# gems-NHD.net
KiCad netlist of a schematic drawn in EAGLE
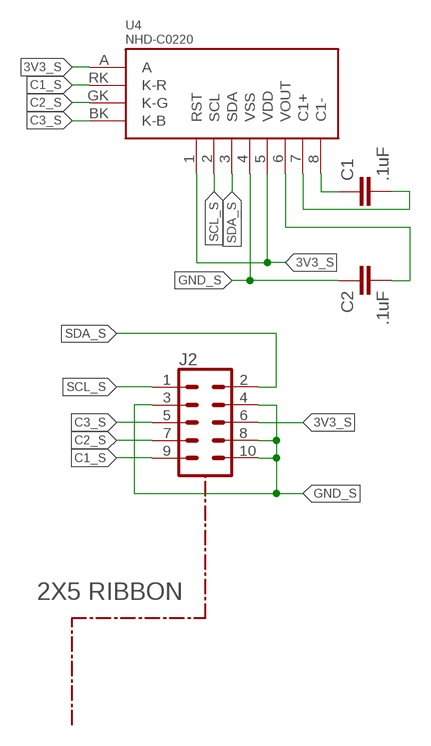
[diagram p0: schematic, sheet 1]

(export (version "E")
  (design (tool "Eeschema 10.0.6"))
  (components
    (comp (ref "C1")
      (value ".1uF")
      (footprint "eagle-import:C025-025X050")
      (libsource (lib "eagle-import") (part "C-EU025-025X050"))
    )
    (comp (ref "C2")
      (value ".1uF")
      (footprint "eagle-import:C025-025X050")
      (libsource (lib "eagle-import") (part "C-EU025-025X050"))
    )
    (comp (ref "J2")
      (value "CONN_05X2SHD-NS")
      (footprint "eagle-import:2X5-SHROUDED-NS")
      (libsource (lib "eagle-import") (part "CONN_05X2SHD-NS"))
    )
    (comp (ref "U4")
      (value "NHD‐C0220")
      (footprint "eagle-import:NHD-C0220")
      (libsource (lib "eagle-import") (part "NHD‐C0220"))
    )
  )
  (nets
    (net (code "1") (name "3V3_S") (class "Default")
      (node (ref "J2") (pin "6") (pinfunction "6_6") (pintype "passive"))
      (node (ref "U4") (pin "1") (pinfunction "RST_1") (pintype "bidirectional"))
      (node (ref "U4") (pin "5") (pinfunction "VDD_5") (pintype "bidirectional"))
      (node (ref "U4") (pin "A") (pinfunction "A_A") (pintype "bidirectional"))
    )
    (net (code "2") (name "C1_S") (class "Default")
      (node (ref "J2") (pin "9") (pinfunction "9_9") (pintype "passive"))
      (node (ref "U4") (pin "RK") (pinfunction "K-R_RK") (pintype "bidirectional"))
    )
    (net (code "3") (name "C2_S") (class "Default")
      (node (ref "J2") (pin "7") (pinfunction "7_7") (pintype "passive"))
      (node (ref "U4") (pin "GK") (pinfunction "K-G_GK") (pintype "bidirectional"))
    )
    (net (code "4") (name "C3_S") (class "Default")
      (node (ref "J2") (pin "5") (pinfunction "5_5") (pintype "passive"))
      (node (ref "U4") (pin "BK") (pinfunction "K-B_BK") (pintype "bidirectional"))
    )
    (net (code "5") (name "GND_S") (class "Default")
      (node (ref "C2") (pin "1") (pinfunction "1_1") (pintype "passive"))
      (node (ref "J2") (pin "10") (pinfunction "10_10") (pintype "passive"))
      (node (ref "J2") (pin "3") (pinfunction "3_3") (pintype "passive"))
      (node (ref "J2") (pin "4") (pinfunction "4_4") (pintype "passive"))
      (node (ref "J2") (pin "8") (pinfunction "8_8") (pintype "passive"))
      (node (ref "U4") (pin "4") (pinfunction "VSS_4") (pintype "bidirectional"))
    )
    (net (code "6") (name "Net-(U4-C1+)") (class "Default")
      (node (ref "C1") (pin "2") (pinfunction "2_2") (pintype "passive"))
      (node (ref "U4") (pin "7") (pinfunction "C1+_7") (pintype "bidirectional"))
    )
    (net (code "7") (name "Net-(U4-C1-)") (class "Default")
      (node (ref "C1") (pin "1") (pinfunction "1_1") (pintype "passive"))
      (node (ref "U4") (pin "8") (pinfunction "C1-_8") (pintype "bidirectional"))
    )
    (net (code "8") (name "Net-(U4-VOUT)") (class "Default")
      (node (ref "C2") (pin "2") (pinfunction "2_2") (pintype "passive"))
      (node (ref "U4") (pin "6") (pinfunction "VOUT_6") (pintype "bidirectional"))
    )
    (net (code "9") (name "SCL_S") (class "Default")
      (node (ref "J2") (pin "1") (pinfunction "1_1") (pintype "passive"))
      (node (ref "U4") (pin "2") (pinfunction "SCL_2") (pintype "bidirectional"))
    )
    (net (code "10") (name "SDA_S") (class "Default")
      (node (ref "J2") (pin "2") (pinfunction "2_2") (pintype "passive"))
      (node (ref "U4") (pin "3") (pinfunction "SDA_3") (pintype "bidirectional"))
    )
  )
)
